# ShutdownSegement.net
KiCad netlist of a schematic drawn in Altium Designer
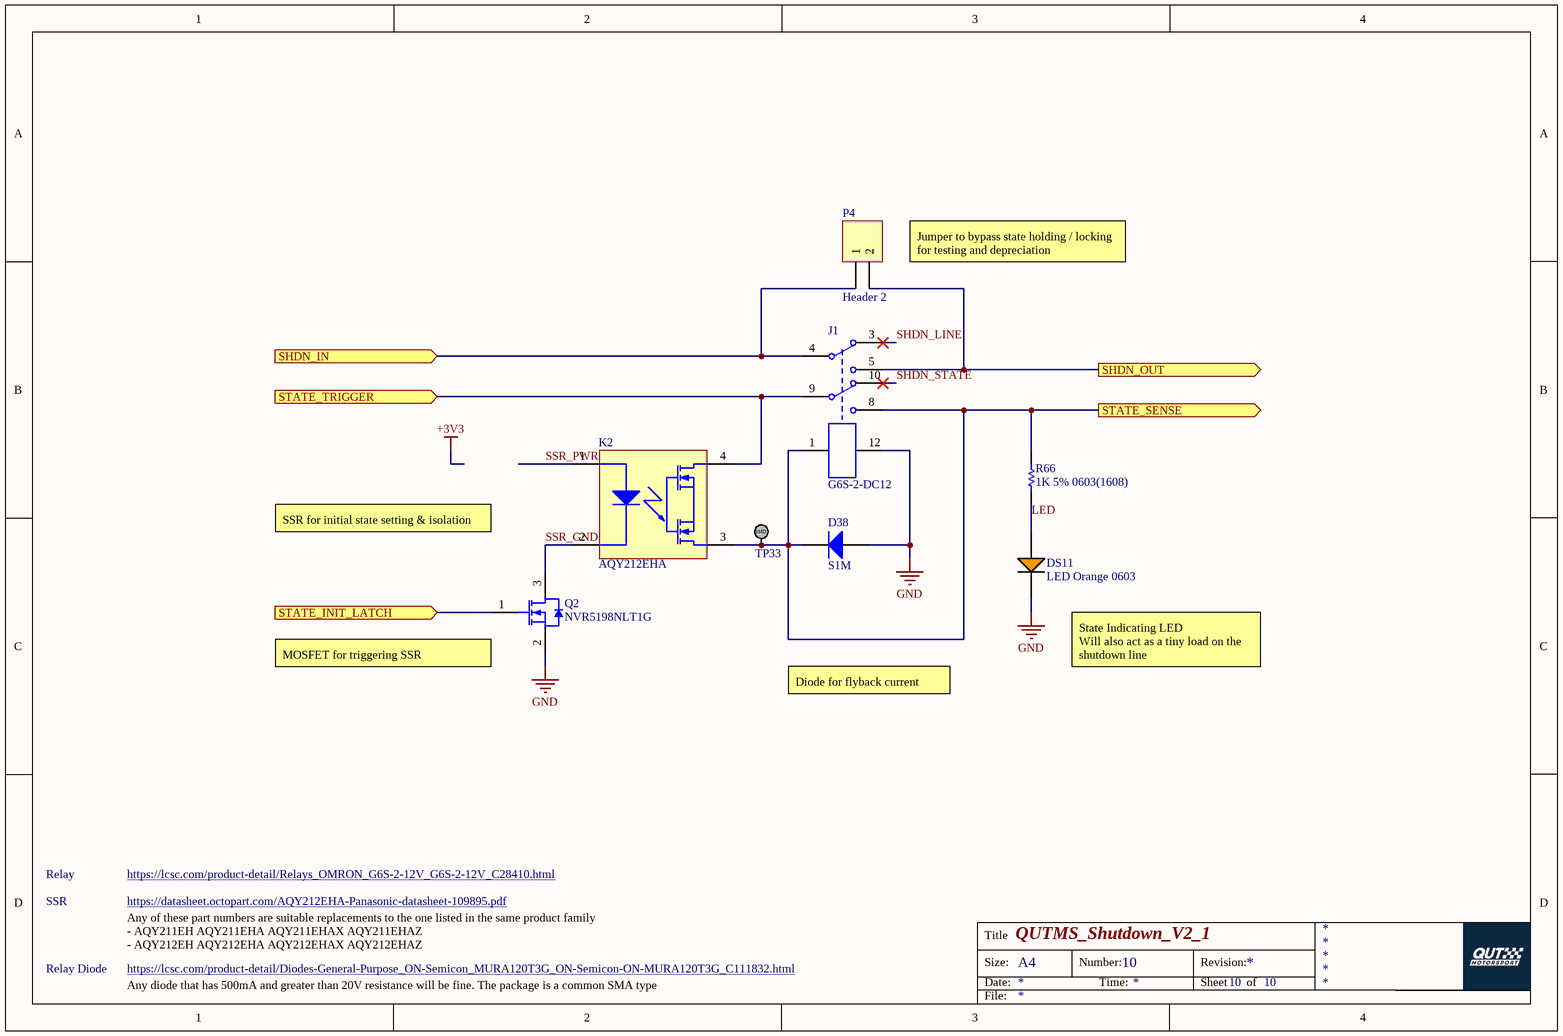
[diagram p0: ShutdownSegement.SchDoc]

(export (version "E")
  (design (tool "Eeschema 10.0.6"))
  (components
    (comp (ref "D38")
      (value "S1M")
      (footprint "FAIR-DO-214AC-2_V")
      (description "General Purpose Rectifier, 1 A, 1000 V, -55 to 150 degC, 2-Pin DO-214AC, RoHS, Tape and Reel")
      (fields (field (name "MANUFACTURER") "Fairchild"))
      (libsource (lib "Altium Content Vault") (part "D-AK-2"))
    )
    (comp (ref "DS11")
      (value "LED Orange 0603")
      (footprint "LED ORANGE 0603")
      (libsource (lib "QUTMS_LEDLibrary") (part "LED ORANGE 0603"))
    )
    (comp (ref "J1")
      (value "G6S-2-DC12")
      (footprint "G6S-2")
      (description "Telecom Non Latching 12VDC DPDT 2A Through Hole Relays RoHS")
      (libsource (lib "QUTMS_RelayLibrary") (part "G6S-2-DC12"))
    )
    (comp (ref "K2")
      (value "AQY212EHA")
      (footprint "PNSC-DIP4(SMT)_V")
      (fields (field (name "MANUFACTURER") "Panasonic"))
      (libsource (lib "Altium Content Vault") (part "PNSC-AQY212EH-DIP4"))
    )
    (comp (ref "P4")
      (value "Header 2")
      (footprint "HDR1X2")
      (description "Header, 2-Pin")
      (fields (field (name "PUBLISHER") "Altium Limited"))
      (libsource (lib "Miscellaneous Connectors") (part "Header 2"))
    )
    (comp (ref "Q2")
      (value "NVR5198NLT1G")
      (footprint "ONSC-SOT-23-3-318-08_V")
      (description "Power MOSFET, 60 V, 155 mOhm, Single N-Channel Logic Level, 3-Pin SOT-23, Pb-Free, Tape and Reel")
      (fields (field (name "MANUFACTURER") "On Semiconductor"))
      (libsource (lib "Altium Content Vault") (part "ONSC-NMOS-G1S2D3-3"))
    )
    (comp (ref "R66")
      (value "1K 5% 0603(1608)")
      (footprint "RESC0603(1608)_L")
      (description "1K 0.1W 5% 0603 (1608 Metric)  SMD")
      (fields (field (name "TOLERANCE") "5 %") (field (name "POWER") "0.1 W"))
      (libsource (lib "Altium Content Vault") (part "RES"))
    )
    (comp (ref "TP33")
      (value "TestPoint_SMD")
      (footprint "TestPointSMD")
      (libsource (lib "StandardTest") (part "TestPoint_SMD"))
    )
  )
  (nets
    (net (code "2") (name "/LED") (class "Default")
      (node (ref "DS11") (pin "1") (pinfunction "A_1") (pintype "passive"))
      (node (ref "R66") (pin "1") (pinfunction "1_1") (pintype "passive"))
    )
    (net (code "3") (name "/SHDN_IN") (class "Default")
      (node (ref "J1") (pin "4") (pinfunction "4_4") (pintype "passive"))
      (node (ref "P4") (pin "1") (pinfunction "1_1") (pintype "passive"))
    )
    (net (code "4") (name "/SHDN_LINE") (class "Default")
      (node (ref "J1") (pin "3") (pinfunction "3_3") (pintype "passive+no_connect"))
    )
    (net (code "5") (name "/SHDN_OUT") (class "Default")
      (node (ref "J1") (pin "5") (pinfunction "5_5") (pintype "passive"))
      (node (ref "P4") (pin "2") (pinfunction "2_2") (pintype "passive"))
    )
    (net (code "6") (name "/SHDN_STATE") (class "Default")
      (node (ref "J1") (pin "10") (pinfunction "10_10") (pintype "passive+no_connect"))
    )
    (net (code "7") (name "/SSR_GND") (class "Default")
      (node (ref "K2") (pin "2") (pinfunction "2_2") (pintype "passive"))
      (node (ref "Q2") (pin "3") (pinfunction "D_3") (pintype "passive"))
    )
    (net (code "8") (name "/SSR_PWR") (class "Default")
      (node (ref "K2") (pin "1") (pinfunction "1_1") (pintype "passive"))
    )
    (net (code "9") (name "/STATE_INIT_LATCH") (class "Default")
      (node (ref "Q2") (pin "1") (pinfunction "G_1") (pintype "passive"))
    )
    (net (code "10") (name "/STATE_SENSE") (class "Default")
      (node (ref "D38") (pin "2") (pinfunction "K_2") (pintype "passive"))
      (node (ref "J1") (pin "1") (pinfunction "1_1") (pintype "passive"))
      (node (ref "J1") (pin "8") (pinfunction "8_8") (pintype "passive"))
      (node (ref "K2") (pin "3") (pinfunction "3_3") (pintype "passive"))
      (node (ref "R66") (pin "2") (pinfunction "2_2") (pintype "passive"))
      (node (ref "TP33") (pin "1") (pinfunction "1_1") (pintype "passive"))
    )
    (net (code "11") (name "/STATE_TRIGGER") (class "Default")
      (node (ref "J1") (pin "9") (pinfunction "9_9") (pintype "passive"))
      (node (ref "K2") (pin "4") (pinfunction "4_4") (pintype "passive"))
    )
    (net (code "12") (name "GND") (class "Default")
      (node (ref "D38") (pin "1") (pinfunction "A_1") (pintype "passive"))
      (node (ref "DS11") (pin "2") (pinfunction "C_2") (pintype "passive"))
      (node (ref "J1") (pin "12") (pinfunction "12_12") (pintype "passive"))
      (node (ref "Q2") (pin "2") (pinfunction "S_2") (pintype "passive"))
    )
  )
)
